# Main_cct.net
KiCad netlist of a schematic drawn in Altium Designer
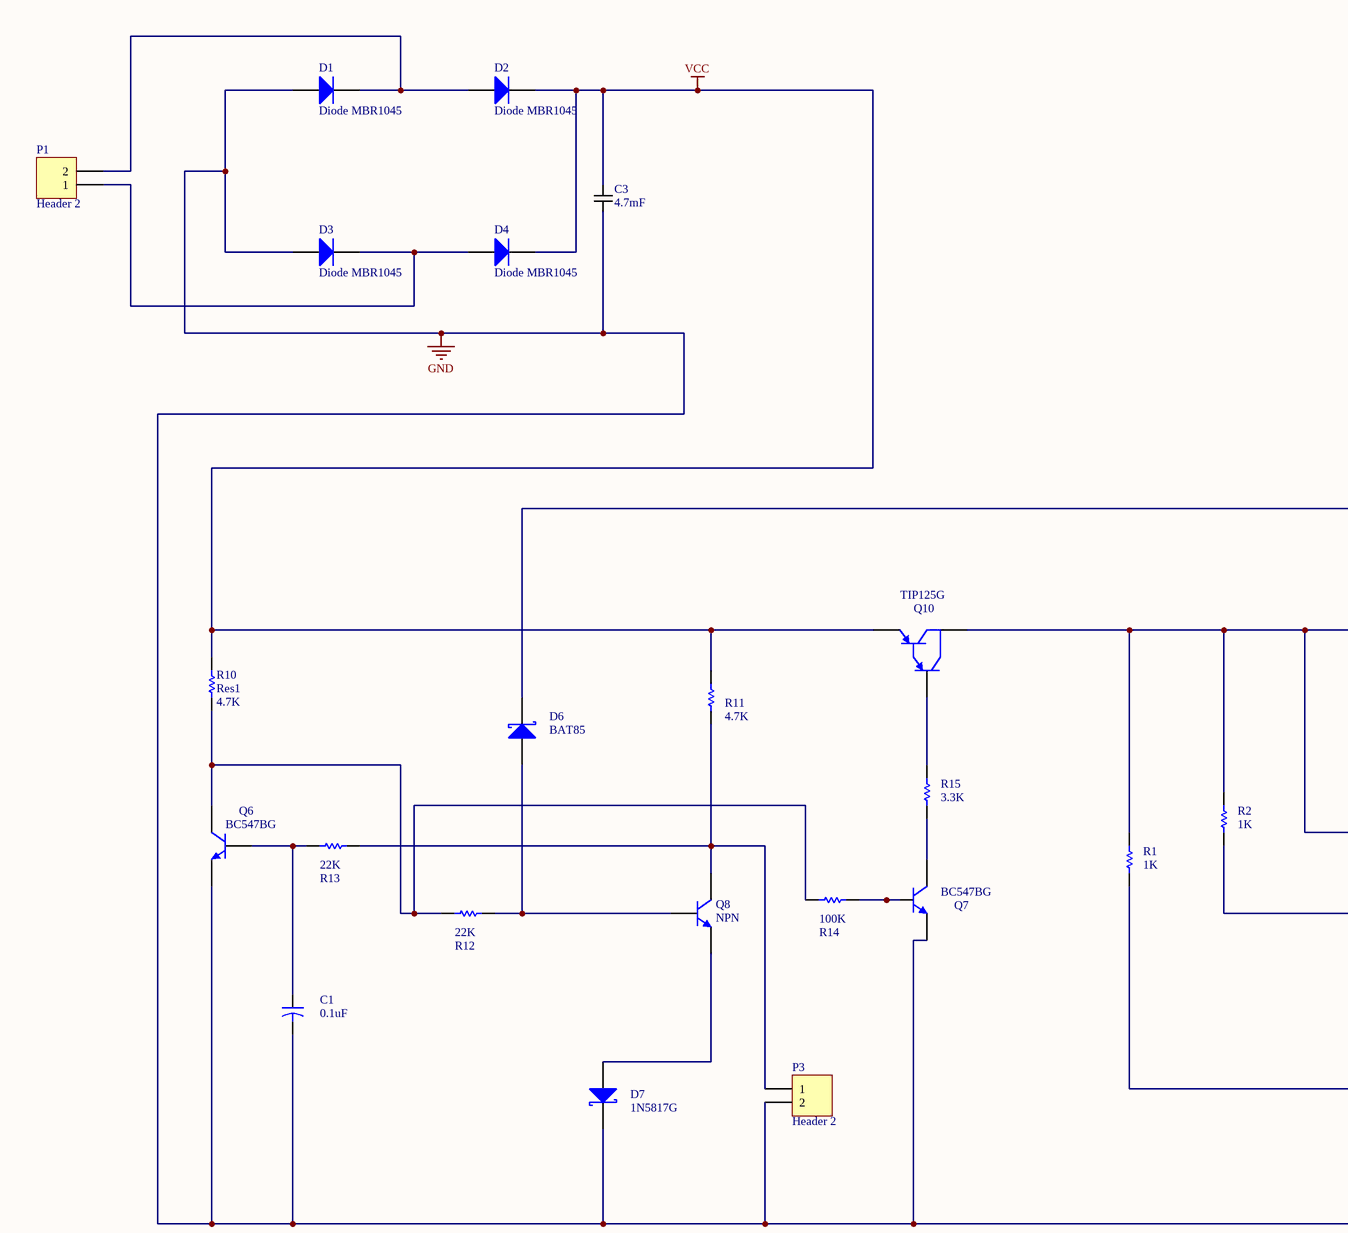
[diagram p0: Main_cct..SchDoc, left]
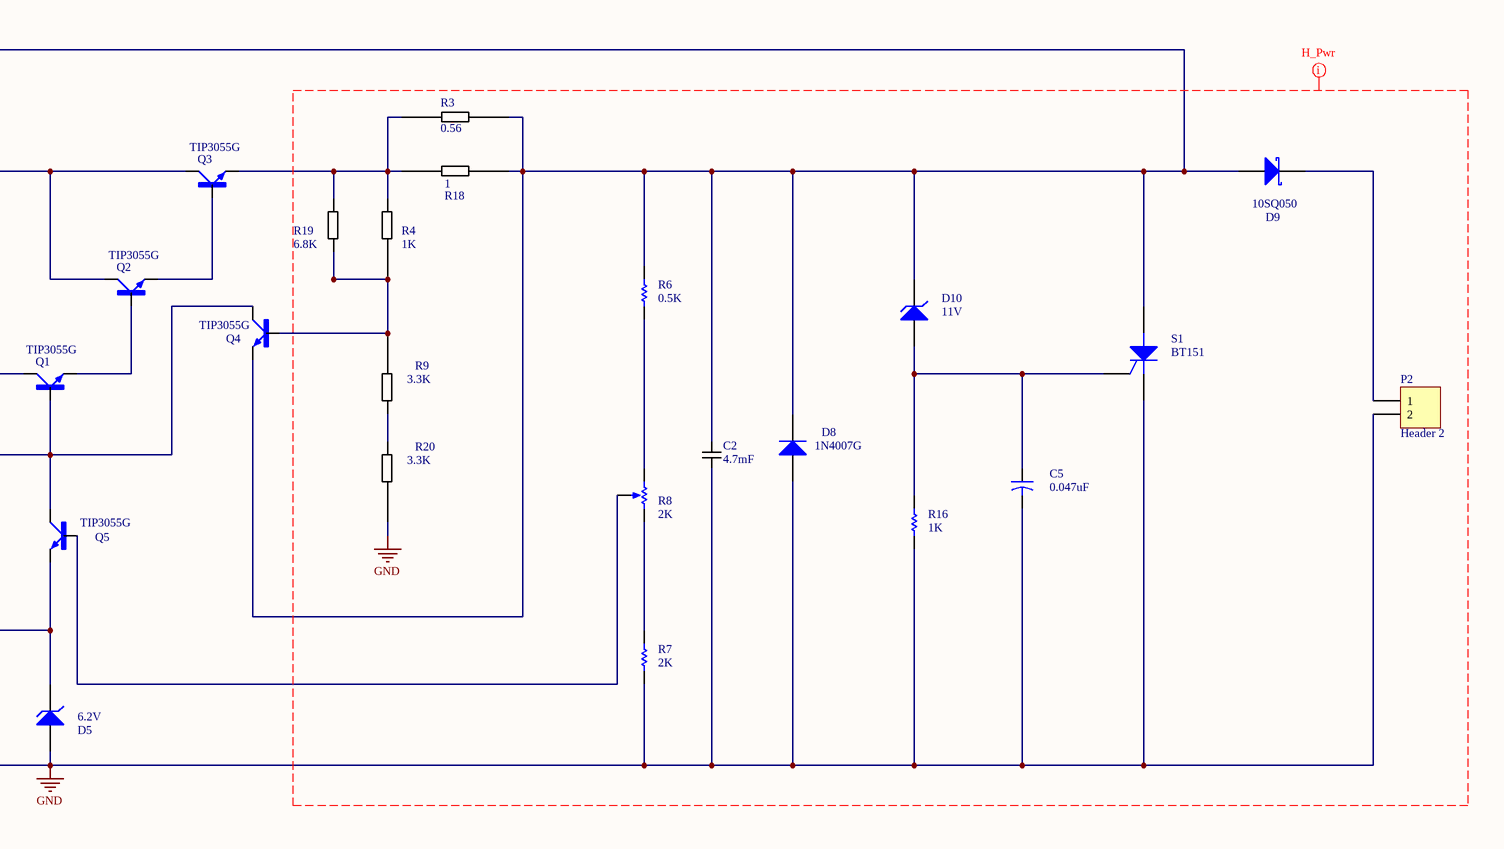
[diagram p1: Main_cct..SchDoc, right]

(export (version "E")
  (design (tool "Eeschema 10.0.6"))
  (components
    (comp (ref "C1")
      (value "0.1uF")
      (footprint "CAPR5-4X5")
      (description "Capacitor")
      (fields (field (name "PUBLISHER") "Altium Limited"))
      (libsource (lib "Miscellaneous Devices") (part "Cap2"))
    )
    (comp (ref "C2")
      (value "4.7mF")
      (footprint "capacitor D 35mm")
      (description "diameter 35mm")
      (libsource (lib "Capacitor_35mm_diameter") (part "Component_1"))
    )
    (comp (ref "C3")
      (value "4.7mF")
      (footprint "capacitor D 35mm")
      (description "diameter 35mm")
      (libsource (lib "Capacitor_35mm_diameter") (part "Component_1"))
    )
    (comp (ref "C5")
      (value "0.047uF")
      (footprint "CAPR5-4X5")
      (description "Capacitor")
      (fields (field (name "PUBLISHER") "Altium Limited"))
      (libsource (lib "Miscellaneous Devices") (part "Cap2"))
    )
    (comp (ref "D1")
      (value "Diode MBR1045")
      (footprint "DO-201AD")
      (description "3 Amp Medium Power Silicon Rectifier Diode")
      (fields (field (name "PUBLISHER") "Altium Limited"))
      (libsource (lib "Miscellaneous Devices") (part "Diode 1N5408"))
    )
    (comp (ref "D2")
      (value "Diode MBR1045")
      (footprint "DO-201AD")
      (description "3 Amp Medium Power Silicon Rectifier Diode")
      (fields (field (name "PUBLISHER") "Altium Limited"))
      (libsource (lib "Miscellaneous Devices") (part "Diode 1N5408"))
    )
    (comp (ref "D3")
      (value "Diode MBR1045")
      (footprint "DO-201AD")
      (description "3 Amp Medium Power Silicon Rectifier Diode")
      (fields (field (name "PUBLISHER") "Altium Limited"))
      (libsource (lib "Miscellaneous Devices") (part "Diode 1N5408"))
    )
    (comp (ref "D4")
      (value "Diode MBR1045")
      (footprint "DO-201AD")
      (description "3 Amp Medium Power Silicon Rectifier Diode")
      (fields (field (name "PUBLISHER") "Altium Limited"))
      (libsource (lib "Miscellaneous Devices") (part "Diode 1N5408"))
    )
    (comp (ref "D5")
      (value "6.2V")
      (footprint "DIODE-0.7")
      (description "Zener Diode")
      (fields (field (name "PUBLISHER") "Altium Limited"))
      (libsource (lib "Miscellaneous Devices") (part "D Zener"))
    )
    (comp (ref "D6")
      (value "BAT85")
      (footprint "DO-204AL")
      (description "Schottky Rectifier")
      (fields (field (name "PUBLISHER") "Altium Limited"))
      (libsource (lib "Miscellaneous Devices") (part "Diode 11DQ03"))
    )
    (comp (ref "D7")
      (value "1N5817G")
      (footprint "DO-204AL")
      (description "Schottky Rectifier")
      (fields (field (name "PUBLISHER") "Altium Limited"))
      (libsource (lib "Miscellaneous Devices") (part "Diode 11DQ03"))
    )
    (comp (ref "D8")
      (value "1N4007G")
      (footprint "DO-201AD")
      (description "3 Amp Medium Power Silicon Rectifier Diode")
      (fields (field (name "PUBLISHER") "Altium Limited"))
      (libsource (lib "Miscellaneous Devices") (part "Diode 1N5408"))
    )
    (comp (ref "D9")
      (value "10SQ050")
      (footprint "resistor 25mm")
      (description "Schottky Rectifier")
      (fields (field (name "PUBLISHER") "Altium Limited"))
      (libsource (lib "Miscellaneous Devices") (part "Diode 11DQ03"))
    )
    (comp (ref "D10")
      (value "11V")
      (footprint "DIODE-0.7")
      (description "1N4741A")
      (fields (field (name "PUBLISHER") "Altium Limited"))
      (libsource (lib "Miscellaneous Devices") (part "D Zener"))
    )
    (comp (ref "P1")
      (value "Header 2")
      (footprint "HDR1X2")
      (description "Header, 2-Pin")
      (fields (field (name "PUBLISHER") "Altium Limited"))
      (libsource (lib "") (part "Header 2_1"))
    )
    (comp (ref "P2")
      (value "Header 2")
      (footprint "HDR1X2")
      (description "Header, 2-Pin")
      (fields (field (name "PUBLISHER") "Altium Limited"))
      (libsource (lib "Miscellaneous Connectors") (part "Header 2"))
    )
    (comp (ref "P3")
      (value "Header 2")
      (footprint "HDR1X2")
      (description "Header, 2-Pin")
      (fields (field (name "PUBLISHER") "Altium Limited"))
      (libsource (lib "Miscellaneous Connectors") (part "Header 2"))
    )
    (comp (ref "Q1")
      (value "TIP3055G")
      (footprint "TOP3AV")
      (description "Tranzistor bipolar _BJT_ NPN 60V 15A 90W Gura de trecere TO-247-3")
      (fields (field (name "MP") "TIP3055") (field (name "MF") "ON Semiconductor"))
      (libsource (lib "") (part "TIP3055_1"))
    )
    (comp (ref "Q2")
      (value "TIP3055G")
      (footprint "TOP3AV")
      (description "Tranzistor bipolar _BJT_ NPN 60V 15A 90W Gura de trecere TO-247-3")
      (fields (field (name "MP") "TIP3055") (field (name "MF") "ON Semiconductor"))
      (libsource (lib "") (part "TIP3055_1"))
    )
    (comp (ref "Q3")
      (value "TIP3055G")
      (footprint "TOP3AV")
      (description "Tranzistor bipolar _BJT_ NPN 60V 15A 90W Gura de trecere TO-247-3")
      (fields (field (name "MP") "TIP3055") (field (name "MF") "ON Semiconductor"))
      (libsource (lib "") (part "TIP3055_1"))
    )
    (comp (ref "Q4")
      (value "TIP3055G")
      (footprint "TOP3AV")
      (description "Tranzistor bipolar _BJT_ NPN 60V 15A 90W Gura de trecere TO-247-3")
      (fields (field (name "MP") "TIP3055") (field (name "MF") "ON Semiconductor"))
      (libsource (lib "TIP3055") (part "TIP3055"))
    )
    (comp (ref "Q5")
      (value "TIP3055G")
      (footprint "TOP3AV")
      (description "Tranzistor bipolar _BJT_ NPN 60V 15A 90W Gura de trecere TO-247-3")
      (fields (field (name "MP") "TIP3055") (field (name "MF") "ON Semiconductor"))
      (libsource (lib "TIP3055") (part "TIP3055"))
    )
    (comp (ref "Q6")
      (value "BC547BG")
      (footprint "TO-262-AA")
      (description "NPN Bipolar Transistor")
      (fields (field (name "PUBLISHER") "Altium Limited"))
      (libsource (lib "Miscellaneous Devices") (part "NPN"))
    )
    (comp (ref "Q7")
      (value "BC547BG")
      (footprint "TO-262-AA")
      (description "NPN Bipolar Transistor")
      (fields (field (name "PUBLISHER") "Altium Limited"))
      (libsource (lib "Miscellaneous Devices") (part "NPN"))
    )
    (comp (ref "Q8")
      (value "NPN")
      (footprint "TO-262-AA")
      (description "NPN Bipolar Transistor")
      (fields (field (name "PUBLISHER") "Altium Limited"))
      (libsource (lib "Miscellaneous Devices") (part "NPN"))
    )
    (comp (ref "Q10")
      (value "TIP125G")
      (footprint "E3")
      (description "PNP Darlington Bipolar Transistor")
      (fields (field (name "PUBLISHER") "Altium Limited"))
      (libsource (lib "Miscellaneous Devices") (part "PNP1"))
    )
    (comp (ref "R1")
      (value "1K")
      (footprint "AXIAL-0.3")
      (description "Resistor")
      (fields (field (name "PUBLISHER") "Altium Limited"))
      (libsource (lib "Miscellaneous Devices") (part "Res1"))
    )
    (comp (ref "R2")
      (value "1K")
      (footprint "AXIAL-0.3")
      (description "Resistor")
      (fields (field (name "PUBLISHER") "Altium Limited"))
      (libsource (lib "Miscellaneous Devices") (part "Res1"))
    )
    (comp (ref "R3")
      (value "0.56")
      (footprint "resistor 25mm")
      (description "25mm length")
      (libsource (lib "Resistor_cement(2.5cm)") (part "Component_1"))
    )
    (comp (ref "R4")
      (value "1K")
      (footprint "resistor 25mm")
      (description "25mm length")
      (libsource (lib "Resistor_cement(2.5cm)") (part "Component_1"))
    )
    (comp (ref "R6")
      (value "0.5K")
      (footprint "AXIAL-0.3")
      (description "Resistor")
      (fields (field (name "PUBLISHER") "Altium Limited"))
      (libsource (lib "Miscellaneous Devices") (part "Res1"))
    )
    (comp (ref "R7")
      (value "2K")
      (footprint "AXIAL-0.3")
      (description "Resistor")
      (fields (field (name "PUBLISHER") "Altium Limited"))
      (libsource (lib "Miscellaneous Devices") (part "Res1"))
    )
    (comp (ref "R8")
      (value "2K")
      (footprint "VR5")
      (description "Potentiometer")
      (fields (field (name "PUBLISHER") "Altium Limited"))
      (libsource (lib "Miscellaneous Devices") (part "RPot"))
    )
    (comp (ref "R9")
      (value "3.3K")
      (footprint "resistor 25mm")
      (description "25mm length")
      (libsource (lib "Resistor_cement(2.5cm)") (part "Component_1"))
    )
    (comp (ref "R10")
      (value "Res1")
      (footprint "AXIAL-0.3")
      (description "Resistor")
      (fields (field (name "ALTIUM_VALUE") "4.7K") (field (name "PUBLISHER") "Altium Limited"))
      (libsource (lib "Miscellaneous Devices") (part "Res1"))
    )
    (comp (ref "R11")
      (value "4.7K")
      (footprint "AXIAL-0.3")
      (description "Resistor")
      (fields (field (name "PUBLISHER") "Altium Limited"))
      (libsource (lib "Miscellaneous Devices") (part "Res1"))
    )
    (comp (ref "R12")
      (value "22K")
      (footprint "AXIAL-0.3")
      (description "Resistor")
      (fields (field (name "PUBLISHER") "Altium Limited"))
      (libsource (lib "Miscellaneous Devices") (part "Res1"))
    )
    (comp (ref "R13")
      (value "22K")
      (footprint "AXIAL-0.3")
      (description "Resistor")
      (fields (field (name "PUBLISHER") "Altium Limited"))
      (libsource (lib "Miscellaneous Devices") (part "Res1"))
    )
    (comp (ref "R14")
      (value "100K")
      (footprint "AXIAL-0.3")
      (description "Resistor")
      (fields (field (name "PUBLISHER") "Altium Limited"))
      (libsource (lib "Miscellaneous Devices") (part "Res1"))
    )
    (comp (ref "R15")
      (value "3.3K")
      (footprint "AXIAL-0.3")
      (description "Resistor")
      (fields (field (name "PUBLISHER") "Altium Limited"))
      (libsource (lib "Miscellaneous Devices") (part "Res1"))
    )
    (comp (ref "R16")
      (value "1K")
      (footprint "AXIAL-0.3")
      (description "Resistor")
      (fields (field (name "PUBLISHER") "Altium Limited"))
      (libsource (lib "Miscellaneous Devices") (part "Res1"))
    )
    (comp (ref "R18")
      (value "1")
      (footprint "resistor 25mm")
      (description "25mm length")
      (libsource (lib "Resistor_cement(2.5cm)") (part "Component_1"))
    )
    (comp (ref "R19")
      (value "6.8K")
      (footprint "resistor 25mm")
      (description "25mm length")
      (libsource (lib "Resistor_cement(2.5cm)") (part "Component_1"))
    )
    (comp (ref "R20")
      (value "3.3K")
      (footprint "resistor 25mm")
      (description "25mm length")
      (libsource (lib "Resistor_cement(2.5cm)") (part "Component_1"))
    )
    (comp (ref "S1")
      (value "BT151")
      (footprint "TO-220-AB")
      (description "Silicon Controlled Rectifier")
      (fields (field (name "PUBLISHER") "Altium Limited"))
      (libsource (lib "Miscellaneous Devices") (part "SCR"))
    )
  )
  (nets
    (net (code "1") (name "GND") (class "Default")
      (node (ref "C1") (pin "2") (pinfunction "2_2") (pintype "passive"))
      (node (ref "C2") (pin "2") (pintype "passive"))
      (node (ref "C3") (pin "2") (pintype "passive"))
      (node (ref "C5") (pin "2") (pinfunction "2_2") (pintype "passive"))
      (node (ref "D1") (pin "1") (pinfunction "A_1") (pintype "passive"))
      (node (ref "D3") (pin "1") (pinfunction "A_1") (pintype "passive"))
      (node (ref "D5") (pin "1") (pinfunction "A_1") (pintype "passive"))
      (node (ref "D7") (pin "2") (pinfunction "K_2") (pintype "passive"))
      (node (ref "D8") (pin "1") (pinfunction "A_1") (pintype "passive"))
      (node (ref "P2") (pin "2") (pinfunction "2_2") (pintype "passive"))
      (node (ref "P3") (pin "2") (pinfunction "2_2") (pintype "passive"))
      (node (ref "Q6") (pin "3") (pinfunction "E_3") (pintype "passive"))
      (node (ref "Q7") (pin "3") (pinfunction "E_3") (pintype "passive"))
      (node (ref "R16") (pin "1") (pinfunction "1_1") (pintype "passive"))
      (node (ref "R20") (pin "1") (pintype "passive"))
      (node (ref "R7") (pin "1") (pinfunction "1_1") (pintype "passive"))
      (node (ref "S1") (pin "3") (pinfunction "K_3") (pintype "passive"))
    )
    (net (code "2") (name "Net-(D1-K)") (class "Default")
      (node (ref "D1") (pin "2") (pinfunction "K_2") (pintype "passive"))
      (node (ref "D2") (pin "1") (pinfunction "A_1") (pintype "passive"))
      (node (ref "P1") (pin "2") (pinfunction "2_2") (pintype "passive"))
    )
    (net (code "3") (name "Net-(D3-K)") (class "Default")
      (node (ref "D3") (pin "2") (pinfunction "K_2") (pintype "passive"))
      (node (ref "D4") (pin "1") (pinfunction "A_1") (pintype "passive"))
      (node (ref "P1") (pin "1") (pinfunction "1_1") (pintype "passive"))
    )
    (net (code "4") (name "Net-(D5-K)") (class "Default")
      (node (ref "D5") (pin "2") (pinfunction "K_2") (pintype "passive"))
      (node (ref "Q5") (pin "E") (pinfunction "E_E") (pintype "passive"))
      (node (ref "R1") (pin "1") (pinfunction "1_1") (pintype "passive"))
    )
    (net (code "5") (name "Net-(D6-A)") (class "Default")
      (node (ref "D6") (pin "1") (pinfunction "A_1") (pintype "passive"))
      (node (ref "Q8") (pin "2") (pinfunction "B_2") (pintype "passive"))
      (node (ref "R12") (pin "1") (pinfunction "1_1") (pintype "passive"))
    )
    (net (code "6") (name "Net-(D7-A)") (class "Default")
      (node (ref "D7") (pin "1") (pinfunction "A_1") (pintype "passive"))
      (node (ref "Q8") (pin "3") (pinfunction "E_3") (pintype "passive"))
    )
    (net (code "7") (name "Net-(D9-K)") (class "Default")
      (node (ref "D9") (pin "2") (pinfunction "K_2") (pintype "passive"))
      (node (ref "P2") (pin "1") (pinfunction "1_1") (pintype "passive"))
    )
    (net (code "8") (name "Net-(D10-A)") (class "Default")
      (node (ref "C5") (pin "1") (pinfunction "1_1") (pintype "passive"))
      (node (ref "D10") (pin "1") (pinfunction "A_1") (pintype "passive"))
      (node (ref "R16") (pin "2") (pinfunction "2_2") (pintype "passive"))
      (node (ref "S1") (pin "2") (pinfunction "G_2") (pintype "passive"))
    )
    (net (code "9") (name "Net-(D10-K)") (class "Default")
      (node (ref "C2") (pin "1") (pintype "passive"))
      (node (ref "D10") (pin "2") (pinfunction "K_2") (pintype "passive"))
      (node (ref "D6") (pin "2") (pinfunction "K_2") (pintype "passive"))
      (node (ref "D8") (pin "2") (pinfunction "K_2") (pintype "passive"))
      (node (ref "D9") (pin "1") (pinfunction "A_1") (pintype "passive"))
      (node (ref "Q4") (pin "E") (pinfunction "E_E") (pintype "passive"))
      (node (ref "R18") (pin "2") (pintype "passive"))
      (node (ref "R3") (pin "2") (pintype "passive"))
      (node (ref "R6") (pin "2") (pinfunction "2_2") (pintype "passive"))
      (node (ref "S1") (pin "1") (pinfunction "A_1") (pintype "passive"))
    )
    (net (code "10") (name "Net-(Q1-PadB)") (class "Default")
      (node (ref "Q1") (pin "B") (pinfunction "B_B") (pintype "passive"))
      (node (ref "Q4") (pin "C") (pinfunction "C_C") (pintype "passive"))
      (node (ref "Q5") (pin "C") (pinfunction "C_C") (pintype "passive"))
      (node (ref "R2") (pin "1") (pinfunction "1_1") (pintype "passive"))
    )
    (net (code "11") (name "Net-(Q1-PadE)") (class "Default")
      (node (ref "Q1") (pin "E") (pinfunction "E_E") (pintype "passive"))
      (node (ref "Q2") (pin "B") (pinfunction "B_B") (pintype "passive"))
    )
    (net (code "12") (name "Net-(Q2-PadE)") (class "Default")
      (node (ref "Q2") (pin "E") (pinfunction "E_E") (pintype "passive"))
      (node (ref "Q3") (pin "B") (pinfunction "B_B") (pintype "passive"))
    )
    (net (code "13") (name "Net-(Q3-PadE)") (class "Default")
      (node (ref "Q3") (pin "E") (pinfunction "E_E") (pintype "passive"))
      (node (ref "R18") (pin "1") (pintype "passive"))
      (node (ref "R19") (pin "2") (pintype "passive"))
      (node (ref "R3") (pin "1") (pintype "passive"))
      (node (ref "R4") (pin "2") (pintype "passive"))
    )
    (net (code "14") (name "Net-(Q4-PadB)") (class "Default")
      (node (ref "Q4") (pin "B") (pinfunction "B_B") (pintype "passive"))
      (node (ref "R19") (pin "1") (pintype "passive"))
      (node (ref "R4") (pin "1") (pintype "passive"))
      (node (ref "R9") (pin "2") (pintype "passive"))
    )
    (net (code "15") (name "Net-(Q6-B)") (class "Default")
      (node (ref "C1") (pin "1") (pinfunction "1_1") (pintype "passive"))
      (node (ref "Q6") (pin "2") (pinfunction "B_2") (pintype "passive"))
      (node (ref "R13") (pin "2") (pinfunction "2_2") (pintype "passive"))
    )
    (net (code "16") (name "Net-(Q6-C)") (class "Default")
      (node (ref "Q6") (pin "1") (pinfunction "C_1") (pintype "passive"))
      (node (ref "R10") (pin "1") (pinfunction "1_1") (pintype "passive"))
      (node (ref "R12") (pin "2") (pinfunction "2_2") (pintype "passive"))
      (node (ref "R14") (pin "2") (pinfunction "2_2") (pintype "passive"))
    )
    (net (code "17") (name "Net-(Q7-B)") (class "Default")
      (node (ref "Q7") (pin "2") (pinfunction "B_2") (pintype "passive"))
      (node (ref "R14") (pin "1") (pinfunction "1_1") (pintype "passive"))
    )
    (net (code "18") (name "Net-(Q7-C)") (class "Default")
      (node (ref "Q7") (pin "1") (pinfunction "C_1") (pintype "passive"))
      (node (ref "R15") (pin "1") (pinfunction "1_1") (pintype "passive"))
    )
    (net (code "19") (name "Net-(Q8-C)") (class "Default")
      (node (ref "P3") (pin "1") (pinfunction "1_1") (pintype "passive"))
      (node (ref "Q8") (pin "1") (pinfunction "C_1") (pintype "passive"))
      (node (ref "R11") (pin "1") (pinfunction "1_1") (pintype "passive"))
      (node (ref "R13") (pin "1") (pinfunction "1_1") (pintype "passive"))
    )
    (net (code "20") (name "Net-(Q10-B)") (class "Default")
      (node (ref "Q10") (pin "2") (pinfunction "B_2") (pintype "passive"))
      (node (ref "R15") (pin "2") (pinfunction "2_2") (pintype "passive"))
    )
    (net (code "21") (name "Net-(Q10-C)") (class "Default")
      (node (ref "Q1") (pin "C") (pinfunction "C_C") (pintype "passive"))
      (node (ref "Q10") (pin "3") (pinfunction "C_3") (pintype "passive"))
      (node (ref "Q2") (pin "C") (pinfunction "C_C") (pintype "passive"))
      (node (ref "Q3") (pin "C") (pinfunction "C_C") (pintype "passive"))
      (node (ref "R1") (pin "2") (pinfunction "2_2") (pintype "passive"))
      (node (ref "R2") (pin "2") (pinfunction "2_2") (pintype "passive"))
    )
    (net (code "22") (name "Net-(R8-BOT)") (class "Default")
      (node (ref "R7") (pin "2") (pinfunction "2_2") (pintype "passive"))
      (node (ref "R8") (pin "2") (pinfunction "BOT_2") (pintype "passive"))
    )
    (net (code "23") (name "Net-(R8-TAP)") (class "Default")
      (node (ref "Q5") (pin "B") (pinfunction "B_B") (pintype "passive"))
      (node (ref "R8") (pin "3") (pinfunction "TAP_3") (pintype "passive"))
    )
    (net (code "24") (name "Net-(R8-TOP)") (class "Default")
      (node (ref "R6") (pin "1") (pinfunction "1_1") (pintype "passive"))
      (node (ref "R8") (pin "1") (pinfunction "TOP_1") (pintype "passive"))
    )
    (net (code "25") (name "Net-(R20-Pad2)") (class "Default")
      (node (ref "R20") (pin "2") (pintype "passive"))
      (node (ref "R9") (pin "1") (pintype "passive"))
    )
    (net (code "26") (name "VCC") (class "Default")
      (node (ref "C3") (pin "1") (pintype "passive"))
      (node (ref "D2") (pin "2") (pinfunction "K_2") (pintype "passive"))
      (node (ref "D4") (pin "2") (pinfunction "K_2") (pintype "passive"))
      (node (ref "Q10") (pin "1") (pinfunction "E_1") (pintype "passive"))
      (node (ref "R10") (pin "2") (pinfunction "2_2") (pintype "passive"))
      (node (ref "R11") (pin "2") (pinfunction "2_2") (pintype "passive"))
    )
  )
)
